# Top_Sheet.net
KiCad netlist of a schematic drawn in Altium Designer
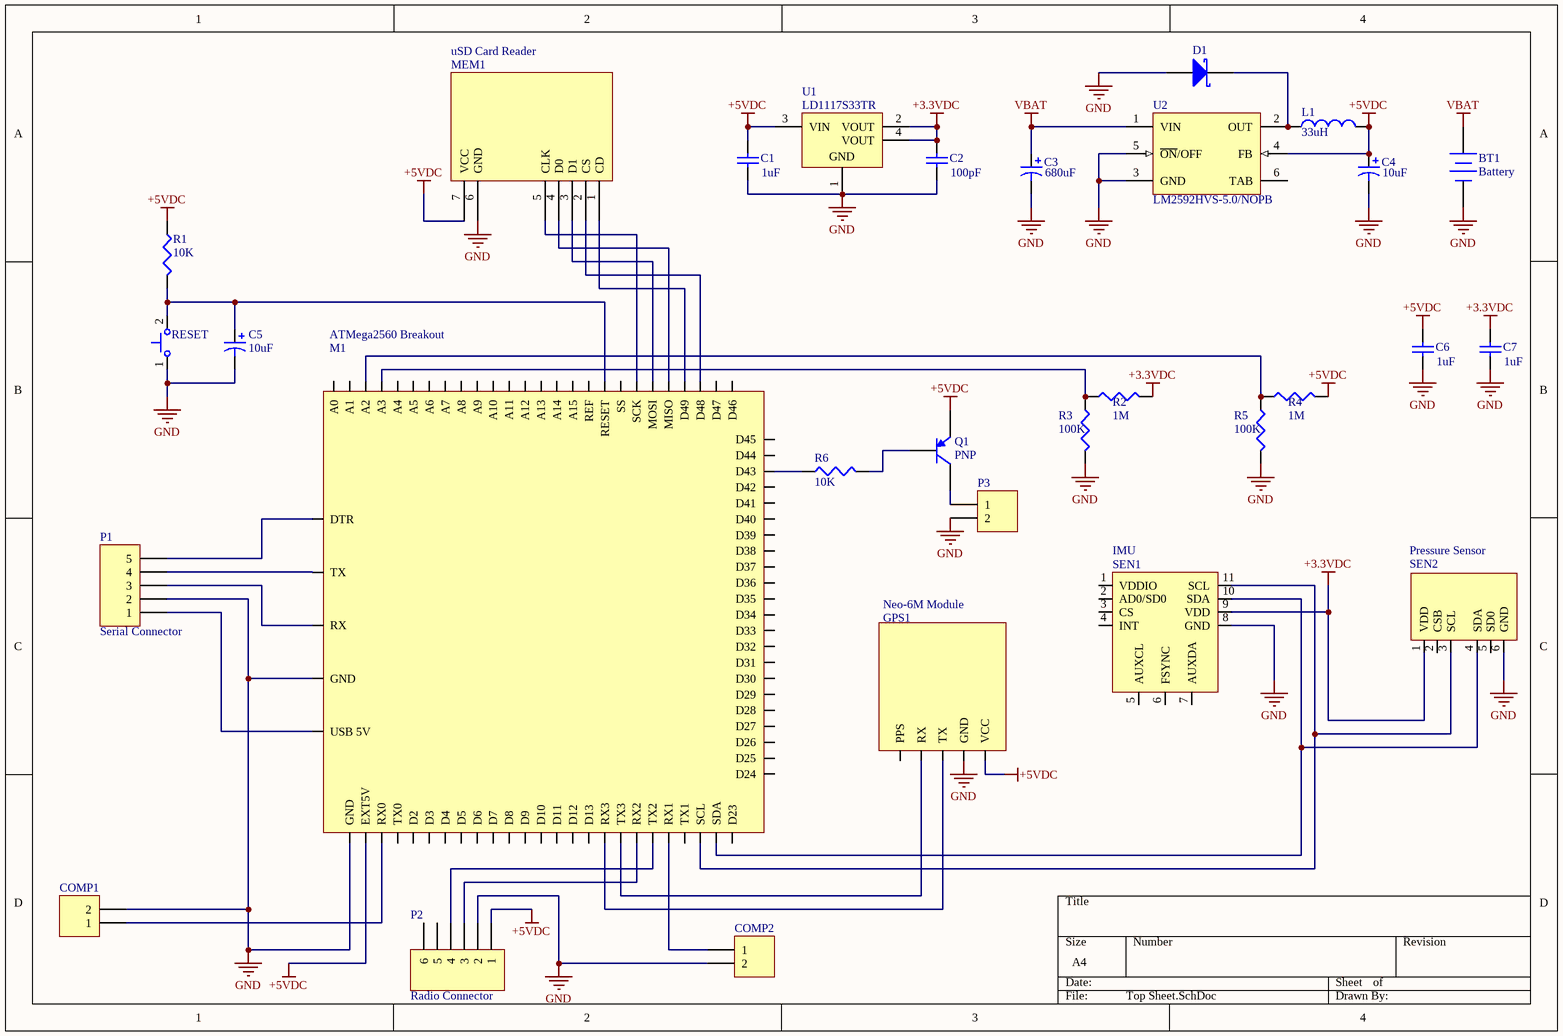
[diagram p0: Top Sheet.SchDoc]

(export (version "E")
  (design (tool "Eeschema 10.0.6"))
  (components
    (comp (ref "BT1")
      (value "Battery")
      (footprint "BAT-2")
      (description "Multicell Battery")
      (fields (field (name "PUBLISHER") "Altium Limited"))
      (libsource (lib "Miscellaneous Devices") (part "Battery"))
    )
    (comp (ref "C1")
      (value "1uF")
      (footprint "C1206")
      (description "Capacitor (Semiconductor SIM Model)")
      (fields (field (name "Comment") "Cap Semi") (field (name "PUBLISHER") "Altium Limited"))
      (libsource (lib "Miscellaneous Devices") (part "Cap Semi"))
    )
    (comp (ref "C2")
      (value "100pF")
      (footprint "C1206")
      (description "Capacitor (Semiconductor SIM Model)")
      (fields (field (name "Comment") "Cap Semi") (field (name "PUBLISHER") "Altium Limited"))
      (libsource (lib "Miscellaneous Devices") (part "Cap Semi"))
    )
    (comp (ref "C3")
      (value "680uF")
      (footprint "RB5-10.5")
      (description "Polarized Capacitor (Surface Mount)")
      (fields (field (name "Comment") "Cap Pol3") (field (name "PUBLISHER") "Altium Limited"))
      (libsource (lib "Miscellaneous Devices") (part "Cap Pol3"))
    )
    (comp (ref "C4")
      (value "10uF")
      (footprint "RB5-10.5")
      (description "Polarized Capacitor (Surface Mount)")
      (fields (field (name "Comment") "Cap Pol3") (field (name "PUBLISHER") "Altium Limited"))
      (libsource (lib "Miscellaneous Devices") (part "Cap Pol3"))
    )
    (comp (ref "C5")
      (value "10uF")
      (footprint "C0805")
      (description "Polarized Capacitor (Surface Mount)")
      (fields (field (name "Comment") "Cap Pol3") (field (name "PUBLISHER") "Altium Limited"))
      (libsource (lib "Miscellaneous Devices") (part "Cap Pol3"))
    )
    (comp (ref "C6")
      (value "1uF")
      (footprint "C1206")
      (description "Capacitor (Semiconductor SIM Model)")
      (fields (field (name "Comment") "Cap Semi") (field (name "PUBLISHER") "Altium Limited"))
      (libsource (lib "Miscellaneous Devices") (part "Cap Semi"))
    )
    (comp (ref "C7")
      (value "1uF")
      (footprint "C1206")
      (description "Capacitor (Semiconductor SIM Model)")
      (fields (field (name "Comment") "Cap Semi") (field (name "PUBLISHER") "Altium Limited"))
      (libsource (lib "Miscellaneous Devices") (part "Cap Semi"))
    )
    (comp (ref "COMP1")
      (value "Header 2")
      (footprint "HDR1X2")
      (description "Header, 2-Pin")
      (fields (field (name "PUBLISHER") "Altium Limited"))
      (libsource (lib "") (part "Header 2_1"))
    )
    (comp (ref "COMP2")
      (value "Header 2")
      (footprint "HDR1X2")
      (description "Header, 2-Pin")
      (fields (field (name "PUBLISHER") "Altium Limited"))
      (libsource (lib "Miscellaneous Connectors") (part "Header 2"))
    )
    (comp (ref "D1")
      (value "D Schottky")
      (footprint "SMB")
      (description "Schottky Diode")
      (fields (field (name "PUBLISHER") "Altium Limited"))
      (libsource (lib "Miscellaneous Devices") (part "D Schottky"))
    )
    (comp (ref "GPS1")
      (value "Neo-6M Module")
      (footprint "Neo-6M GPS Module")
      (description "Serial GPS module")
      (libsource (lib "SensorLib") (part "Neo-6M Module"))
    )
    (comp (ref "L1")
      (value "33uH")
      (footprint "Inductor")
      (description "Inductor")
      (fields (field (name "PUBLISHER") "Altium Limited"))
      (libsource (lib "Miscellaneous Devices") (part "Inductor"))
    )
    (comp (ref "M1")
      (value "ATMega2560 Breakout")
      (footprint "ATMEGA2560 Breakout")
      (description "Tindie's breakout board for the ATMega2560")
      (libsource (lib "SensorLib") (part "ATMega2560 Breakout"))
    )
    (comp (ref "MEM1")
      (value "uSD Card Reader")
      (footprint "uSD Card Reader")
      (description "SPI interface micro SD card reader from sparkfun.")
      (libsource (lib "SensorLib") (part "uSD Card Reader"))
    )
    (comp (ref "P1")
      (value "Serial Connector")
      (footprint "HDR1X5")
      (description "Header, 5-Pin")
      (fields (field (name "PUBLISHER") "Altium Limited"))
      (libsource (lib "Miscellaneous Connectors") (part "Header 5"))
    )
    (comp (ref "P2")
      (value "Radio Connector")
      (footprint "HDR1X6")
      (description "Header, 6-Pin")
      (fields (field (name "PUBLISHER") "Altium Limited"))
      (libsource (lib "Miscellaneous Connectors") (part "Header 6"))
    )
    (comp (ref "P3")
      (value "Header 2")
      (footprint "HDR1X2")
      (description "Header, 2-Pin")
      (fields (field (name "PUBLISHER") "Altium Limited"))
      (libsource (lib "Miscellaneous Connectors") (part "Header 2"))
    )
    (comp (ref "Q1")
      (value "PNP")
      (footprint "SOT-23B_N")
      (description "PNP Bipolar Transistor")
      (fields (field (name "PUBLISHER") "Altium Limited"))
      (libsource (lib "Miscellaneous Devices") (part "PNP"))
    )
    (comp (ref "R1")
      (value "10K")
      (footprint "6-0805_L")
      (description "Resistor")
      (fields (field (name "Comment") "Res3") (field (name "PUBLISHER") "Altium Limited"))
      (libsource (lib "Miscellaneous Devices") (part "Res3"))
    )
    (comp (ref "R2")
      (value "1M")
      (footprint "6-0805_L")
      (description "Resistor")
      (fields (field (name "Comment") "Res3") (field (name "PUBLISHER") "Altium Limited"))
      (libsource (lib "Miscellaneous Devices") (part "Res3"))
    )
    (comp (ref "R3")
      (value "100K")
      (footprint "6-0805_L")
      (description "Resistor")
      (fields (field (name "Comment") "Res3") (field (name "PUBLISHER") "Altium Limited"))
      (libsource (lib "Miscellaneous Devices") (part "Res3"))
    )
    (comp (ref "R4")
      (value "1M")
      (footprint "6-0805_L")
      (description "Resistor")
      (fields (field (name "Comment") "Res3") (field (name "PUBLISHER") "Altium Limited"))
      (libsource (lib "Miscellaneous Devices") (part "Res3"))
    )
    (comp (ref "R5")
      (value "100K")
      (footprint "6-0805_L")
      (description "Resistor")
      (fields (field (name "Comment") "Res3") (field (name "PUBLISHER") "Altium Limited"))
      (libsource (lib "Miscellaneous Devices") (part "Res3"))
    )
    (comp (ref "R6")
      (value "10K")
      (footprint "6-0805_L")
      (description "Resistor")
      (fields (field (name "Comment") "Res3") (field (name "PUBLISHER") "Altium Limited"))
      (libsource (lib "Miscellaneous Devices") (part "Res3"))
    )
    (comp (ref "RESET")
      (value "KSS221GLFS")
      (footprint "KSS-2G")
      (fields (field (name "PUBLISHER") "Altium Limited"))
      (libsource (lib "CK Switch") (part "KSS221GLFS"))
    )
    (comp (ref "SEN1")
      (value "IMU")
      (footprint "Sparkfun IMU")
      (description "MPU-9250 breakout board from sparkfun.")
      (libsource (lib "SensorLib") (part "Inertial Measurement Unit"))
    )
    (comp (ref "SEN2")
      (value "Pressure Sensor")
      (footprint "Barometric Pressure Sensor")
      (description "MS5611-01BA03 Barometric Pressure Sensor, Variometer.")
      (libsource (lib "SensorLib") (part "Baromateric Pressure Sensor"))
    )
    (comp (ref "U1")
      (value "LD1117S33TR")
      (footprint "SOT-223_N")
      (description "Fixed Low Drop Positive Voltage Regulator, 3.3V, 4-Pin SOT-223, Tape and Reel")
      (libsource (lib "STMicroelectronics Power Management Linear Regulator") (part "LD1117S33TR"))
    )
    (comp (ref "U2")
      (value "LM2592HVS-5.0/NOPB")
      (footprint "TS5B_N")
      (description "SIMPLE SWITCHER® Power Converter 150 KHz 2A Step-Down Voltage Regulator, 5-pin TO-263, Pb-Free")
      (fields
        (field (name "MANUFACTURER") "National Semiconductor")
        (field (name "PUBLISHER") "Altium Limited")
      )
      (libsource (lib "NSC Switcher") (part "LM2592HVS-5.0/NOPB"))
    )
  )
  (nets
    (net (code "1") (name "+3.3VDC") (class "Default")
      (node (ref "C2") (pin "2") (pinfunction "2_2") (pintype "passive"))
      (node (ref "C7") (pin "2") (pinfunction "2_2") (pintype "passive"))
      (node (ref "R2") (pin "2") (pinfunction "2_2") (pintype "passive"))
      (node (ref "SEN1") (pin "9") (pinfunction "VDD_9") (pintype "passive"))
      (node (ref "SEN2") (pin "1") (pinfunction "VDD_1") (pintype "passive"))
      (node (ref "U1") (pin "2") (pinfunction "VOUT_2") (pintype "power_in"))
      (node (ref "U1") (pin "4") (pinfunction "VOUT_4") (pintype "power_in"))
    )
    (net (code "2") (name "+5VDC") (class "Default")
      (node (ref "C1") (pin "2") (pinfunction "2_2") (pintype "passive"))
      (node (ref "C4") (pin "1") (pinfunction "1_1") (pintype "passive"))
      (node (ref "C6") (pin "2") (pinfunction "2_2") (pintype "passive"))
      (node (ref "GPS1") (pin "5") (pinfunction "VCC_5") (pintype "passive"))
      (node (ref "L1") (pin "2") (pinfunction "2_2") (pintype "passive"))
      (node (ref "M1") (pin "EXT5V") (pinfunction "EXT5V_EXT5V") (pintype "passive"))
      (node (ref "MEM1") (pin "7") (pinfunction "VCC_7") (pintype "passive"))
      (node (ref "P2") (pin "1") (pinfunction "1_1") (pintype "passive"))
      (node (ref "Q1") (pin "3") (pinfunction "E_3") (pintype "passive"))
      (node (ref "R1") (pin "1") (pinfunction "1_1") (pintype "passive"))
      (node (ref "R4") (pin "2") (pinfunction "2_2") (pintype "passive"))
      (node (ref "U1") (pin "3") (pinfunction "VIN_3") (pintype "power_in"))
      (node (ref "U2") (pin "4") (pinfunction "FB_4") (pintype "input"))
    )
    (net (code "3") (name "GND") (class "Default")
      (node (ref "BT1") (pin "2") (pinfunction "-_2") (pintype "passive"))
      (node (ref "C1") (pin "1") (pinfunction "1_1") (pintype "passive"))
      (node (ref "C2") (pin "1") (pinfunction "1_1") (pintype "passive"))
      (node (ref "C3") (pin "2") (pinfunction "2_2") (pintype "passive"))
      (node (ref "C4") (pin "2") (pinfunction "2_2") (pintype "passive"))
      (node (ref "C5") (pin "2") (pinfunction "2_2") (pintype "passive"))
      (node (ref "C6") (pin "1") (pinfunction "1_1") (pintype "passive"))
      (node (ref "C7") (pin "1") (pinfunction "1_1") (pintype "passive"))
      (node (ref "COMP1") (pin "2") (pinfunction "2_2") (pintype "passive"))
      (node (ref "COMP2") (pin "2") (pinfunction "2_2") (pintype "passive"))
      (node (ref "D1") (pin "1") (pinfunction "A_1") (pintype "passive"))
      (node (ref "GPS1") (pin "4") (pinfunction "GND_4") (pintype "passive"))
      (node (ref "M1") (pin "GND") (pinfunction "GND_GND") (pintype "passive"))
      (node (ref "MEM1") (pin "6") (pinfunction "GND_6") (pintype "passive"))
      (node (ref "P1") (pin "2") (pinfunction "2_2") (pintype "passive"))
      (node (ref "P2") (pin "2") (pinfunction "2_2") (pintype "passive"))
      (node (ref "P3") (pin "2") (pinfunction "2_2") (pintype "passive"))
      (node (ref "R3") (pin "2") (pinfunction "2_2") (pintype "passive"))
      (node (ref "R5") (pin "2") (pinfunction "2_2") (pintype "passive"))
      (node (ref "RESET") (pin "1") (pinfunction "1_1") (pintype "passive"))
      (node (ref "SEN1") (pin "8") (pinfunction "GND_8") (pintype "passive"))
      (node (ref "SEN2") (pin "6") (pinfunction "GND_6") (pintype "passive"))
      (node (ref "U1") (pin "1") (pinfunction "GND_1") (pintype "power_in"))
      (node (ref "U2") (pin "3") (pinfunction "GND_3") (pintype "power_in"))
      (node (ref "U2") (pin "5") (pinfunction "~{ON}/OFF_5") (pintype "input"))
    )
    (net (code "4") (name "Net-(C5-Pad1)") (class "Default")
      (node (ref "C5") (pin "1") (pinfunction "1_1") (pintype "passive"))
      (node (ref "M1") (pin "RESET") (pinfunction "RESET_RESET") (pintype "passive"))
      (node (ref "R1") (pin "2") (pinfunction "2_2") (pintype "passive"))
      (node (ref "RESET") (pin "2") (pinfunction "2_2") (pintype "passive"))
    )
    (net (code "5") (name "Net-(COMP1-Pad1)") (class "Default")
      (node (ref "COMP1") (pin "1") (pinfunction "1_1") (pintype "passive"))
      (node (ref "M1") (pin "RX0") (pinfunction "RX0_RX0") (pintype "passive"))
    )
    (net (code "6") (name "Net-(COMP2-Pad1)") (class "Default")
      (node (ref "COMP2") (pin "1") (pinfunction "1_1") (pintype "passive"))
      (node (ref "M1") (pin "RX1") (pinfunction "RX1_RX1") (pintype "passive"))
    )
    (net (code "7") (name "Net-(D1-K)") (class "Default")
      (node (ref "D1") (pin "2") (pinfunction "K_2") (pintype "passive"))
      (node (ref "L1") (pin "1") (pinfunction "1_1") (pintype "passive"))
      (node (ref "U2") (pin "2") (pinfunction "OUT_2") (pintype "power_in"))
    )
    (net (code "8") (name "Net-(GPS1-RX)") (class "Default")
      (node (ref "GPS1") (pin "2") (pinfunction "RX_2") (pintype "passive"))
      (node (ref "M1") (pin "TX3") (pinfunction "TX3_TX3") (pintype "passive"))
    )
    (net (code "9") (name "Net-(GPS1-TX)") (class "Default")
      (node (ref "GPS1") (pin "3") (pinfunction "TX_3") (pintype "passive"))
      (node (ref "M1") (pin "RX3") (pinfunction "RX3_RX3") (pintype "passive"))
    )
    (net (code "10") (name "Net-(M1-D43)") (class "Default")
      (node (ref "M1") (pin "43") (pinfunction "D43_43") (pintype "passive"))
      (node (ref "R6") (pin "1") (pinfunction "1_1") (pintype "passive"))
    )
    (net (code "11") (name "Net-(M1-D48)") (class "Default")
      (node (ref "M1") (pin "48") (pinfunction "D48_48") (pintype "passive"))
      (node (ref "MEM1") (pin "2") (pinfunction "CS_2") (pintype "passive"))
    )
    (net (code "12") (name "Net-(M1-D49)") (class "Default")
      (node (ref "M1") (pin "49") (pinfunction "D49_49") (pintype "passive"))
      (node (ref "MEM1") (pin "1") (pinfunction "CD_1") (pintype "passive"))
    )
    (net (code "13") (name "Net-(M1-PadA2)") (class "Default")
      (node (ref "M1") (pin "A2") (pinfunction "A2_A2") (pintype "passive"))
      (node (ref "R4") (pin "1") (pinfunction "1_1") (pintype "passive"))
      (node (ref "R5") (pin "1") (pinfunction "1_1") (pintype "passive"))
    )
    (net (code "14") (name "Net-(M1-PadA3)") (class "Default")
      (node (ref "M1") (pin "A3") (pinfunction "A3_A3") (pintype "passive"))
      (node (ref "R2") (pin "1") (pinfunction "1_1") (pintype "passive"))
      (node (ref "R3") (pin "1") (pinfunction "1_1") (pintype "passive"))
    )
    (net (code "15") (name "Net-(M1-PadDTR)") (class "Default")
      (node (ref "M1") (pin "DTR") (pinfunction "DTR_DTR") (pintype "passive"))
      (node (ref "P1") (pin "5") (pinfunction "5_5") (pintype "passive"))
    )
    (net (code "16") (name "Net-(M1-PadRX)") (class "Default")
      (node (ref "M1") (pin "RX") (pinfunction "RX_RX") (pintype "passive"))
      (node (ref "P1") (pin "3") (pinfunction "3_3") (pintype "passive"))
    )
    (net (code "17") (name "Net-(M1-PadRX2)") (class "Default")
      (node (ref "M1") (pin "RX2") (pinfunction "RX2_RX2") (pintype "passive"))
      (node (ref "P2") (pin "3") (pinfunction "3_3") (pintype "passive"))
    )
    (net (code "18") (name "Net-(M1-PadTX)") (class "Default")
      (node (ref "M1") (pin "TX") (pinfunction "TX_TX") (pintype "passive"))
      (node (ref "P1") (pin "4") (pinfunction "4_4") (pintype "passive"))
    )
    (net (code "19") (name "Net-(M1-PadTX2)") (class "Default")
      (node (ref "M1") (pin "TX2") (pinfunction "TX2_TX2") (pintype "passive"))
      (node (ref "P2") (pin "4") (pinfunction "4_4") (pintype "passive"))
    )
    (net (code "20") (name "Net-(M1-PadUSB_5V)") (class "Default")
      (node (ref "M1") (pin "USB_5V") (pinfunction "USB_5V_USB_5V") (pintype "passive"))
      (node (ref "P1") (pin "1") (pinfunction "1_1") (pintype "passive"))
    )
    (net (code "21") (name "Net-(MEM1-CLK)") (class "Default")
      (node (ref "M1") (pin "SCK") (pinfunction "SCK_SCK") (pintype "passive"))
      (node (ref "MEM1") (pin "5") (pinfunction "CLK_5") (pintype "passive"))
    )
    (net (code "22") (name "Net-(MEM1-D0)") (class "Default")
      (node (ref "M1") (pin "MISO") (pinfunction "MISO_MISO") (pintype "passive"))
      (node (ref "MEM1") (pin "4") (pinfunction "D0_4") (pintype "passive"))
    )
    (net (code "23") (name "Net-(MEM1-D1)") (class "Default")
      (node (ref "M1") (pin "MOSI") (pinfunction "MOSI_MOSI") (pintype "passive"))
      (node (ref "MEM1") (pin "3") (pinfunction "D1_3") (pintype "passive"))
    )
    (net (code "24") (name "Net-(Q1-B)") (class "Default")
      (node (ref "Q1") (pin "2") (pinfunction "B_2") (pintype "passive"))
      (node (ref "R6") (pin "2") (pinfunction "2_2") (pintype "passive"))
    )
    (net (code "25") (name "Net-(Q1-C)") (class "Default")
      (node (ref "P3") (pin "1") (pinfunction "1_1") (pintype "passive"))
      (node (ref "Q1") (pin "1") (pinfunction "C_1") (pintype "passive"))
    )
    (net (code "26") (name "Net-(SEN1-SCL)") (class "Default")
      (node (ref "M1") (pin "SCL") (pinfunction "SCL_SCL") (pintype "passive"))
      (node (ref "SEN1") (pin "11") (pinfunction "SCL_11") (pintype "passive"))
      (node (ref "SEN2") (pin "3") (pinfunction "SCL_3") (pintype "passive"))
    )
    (net (code "27") (name "Net-(SEN1-SDA)") (class "Default")
      (node (ref "M1") (pin "SDA") (pinfunction "SDA_SDA") (pintype "passive"))
      (node (ref "SEN1") (pin "10") (pinfunction "SDA_10") (pintype "passive"))
      (node (ref "SEN2") (pin "4") (pinfunction "SDA_4") (pintype "passive"))
    )
    (net (code "28") (name "VBAT") (class "Default")
      (node (ref "BT1") (pin "1") (pinfunction "+_1") (pintype "passive"))
      (node (ref "C3") (pin "1") (pinfunction "1_1") (pintype "passive"))
      (node (ref "U2") (pin "1") (pinfunction "VIN_1") (pintype "power_in"))
    )
    (net (code "29") (name "unconnected-(GPS1-PPS-Pad1)") (class "Default")
      (node (ref "GPS1") (pin "1") (pinfunction "PPS_1") (pintype "passive"))
    )
    (net (code "30") (name "unconnected-(M1-D2-Pad2)") (class "Default")
      (node (ref "M1") (pin "2") (pinfunction "D2_2") (pintype "passive"))
    )
    (net (code "31") (name "unconnected-(M1-D3-Pad3)") (class "Default")
      (node (ref "M1") (pin "3") (pinfunction "D3_3") (pintype "passive"))
    )
    (net (code "32") (name "unconnected-(M1-D4-Pad4)") (class "Default")
      (node (ref "M1") (pin "4") (pinfunction "D4_4") (pintype "passive"))
    )
    (net (code "33") (name "unconnected-(M1-D5-Pad5)") (class "Default")
      (node (ref "M1") (pin "5") (pinfunction "D5_5") (pintype "passive"))
    )
    (net (code "34") (name "unconnected-(M1-D6-Pad6)") (class "Default")
      (node (ref "M1") (pin "6") (pinfunction "D6_6") (pintype "passive"))
    )
    (net (code "35") (name "unconnected-(M1-D7-Pad7)") (class "Default")
      (node (ref "M1") (pin "7") (pinfunction "D7_7") (pintype "passive"))
    )
    (net (code "36") (name "unconnected-(M1-D8-Pad8)") (class "Default")
      (node (ref "M1") (pin "8") (pinfunction "D8_8") (pintype "passive"))
    )
    (net (code "37") (name "unconnected-(M1-D9-Pad9)") (class "Default")
      (node (ref "M1") (pin "9") (pinfunction "D9_9") (pintype "passive"))
    )
    (net (code "38") (name "unconnected-(M1-D10-Pad10)") (class "Default")
      (node (ref "M1") (pin "10") (pinfunction "D10_10") (pintype "passive"))
    )
    (net (code "39") (name "unconnected-(M1-D11-Pad11)") (class "Default")
      (node (ref "M1") (pin "11") (pinfunction "D11_11") (pintype "passive"))
    )
    (net (code "40") (name "unconnected-(M1-D12-Pad12)") (class "Default")
      (node (ref "M1") (pin "12") (pinfunction "D12_12") (pintype "passive"))
    )
    (net (code "41") (name "unconnected-(M1-D13-Pad13)") (class "Default")
      (node (ref "M1") (pin "13") (pinfunction "D13_13") (pintype "passive"))
    )
    (net (code "42") (name "unconnected-(M1-D23-Pad23)") (class "Default")
      (node (ref "M1") (pin "23") (pinfunction "D23_23") (pintype "passive"))
    )
    (net (code "43") (name "unconnected-(M1-D24-Pad24)") (class "Default")
      (node (ref "M1") (pin "24") (pinfunction "D24_24") (pintype "passive"))
    )
    (net (code "44") (name "unconnected-(M1-D25-Pad25)") (class "Default")
      (node (ref "M1") (pin "25") (pinfunction "D25_25") (pintype "passive"))
    )
    (net (code "45") (name "unconnected-(M1-D26-Pad26)") (class "Default")
      (node (ref "M1") (pin "26") (pinfunction "D26_26") (pintype "passive"))
    )
    (net (code "46") (name "unconnected-(M1-D27-Pad27)") (class "Default")
      (node (ref "M1") (pin "27") (pinfunction "D27_27") (pintype "passive"))
    )
    (net (code "47") (name "unconnected-(M1-D28-Pad28)") (class "Default")
      (node (ref "M1") (pin "28") (pinfunction "D28_28") (pintype "passive"))
    )
    (net (code "48") (name "unconnected-(M1-D29-Pad29)") (class "Default")
      (node (ref "M1") (pin "29") (pinfunction "D29_29") (pintype "passive"))
    )
    (net (code "49") (name "unconnected-(M1-D30-Pad30)") (class "Default")
      (node (ref "M1") (pin "30") (pinfunction "D30_30") (pintype "passive"))
    )
    (net (code "50") (name "unconnected-(M1-D31-Pad31)") (class "Default")
      (node (ref "M1") (pin "31") (pinfunction "D31_31") (pintype "passive"))
    )
    (net (code "51") (name "unconnected-(M1-D32-Pad32)") (class "Default")
      (node (ref "M1") (pin "32") (pinfunction "D32_32") (pintype "passive"))
    )
    (net (code "52") (name "unconnected-(M1-D33-Pad33)") (class "Default")
      (node (ref "M1") (pin "33") (pinfunction "D33_33") (pintype "passive"))
    )
    (net (code "53") (name "unconnected-(M1-D34-Pad34)") (class "Default")
      (node (ref "M1") (pin "34") (pinfunction "D34_34") (pintype "passive"))
    )
    (net (code "54") (name "unconnected-(M1-D35-Pad35)") (class "Default")
      (node (ref "M1") (pin "35") (pinfunction "D35_35") (pintype "passive"))
    )
    (net (code "55") (name "unconnected-(M1-D36-Pad36)") (class "Default")
      (node (ref "M1") (pin "36") (pinfunction "D36_36") (pintype "passive"))
    )
    (net (code "56") (name "unconnected-(M1-D37-Pad37)") (class "Default")
      (node (ref "M1") (pin "37") (pinfunction "D37_37") (pintype "passive"))
    )
    (net (code "57") (name "unconnected-(M1-D38-Pad38)") (class "Default")
      (node (ref "M1") (pin "38") (pinfunction "D38_38") (pintype "passive"))
    )
    (net (code "58") (name "unconnected-(M1-D39-Pad39)") (class "Default")
      (node (ref "M1") (pin "39") (pinfunction "D39_39") (pintype "passive"))
    )
    (net (code "59") (name "unconnected-(M1-D40-Pad40)") (class "Default")
      (node (ref "M1") (pin "40") (pinfunction "D40_40") (pintype "passive"))
    )
    (net (code "60") (name "unconnected-(M1-D41-Pad41)") (class "Default")
      (node (ref "M1") (pin "41") (pinfunction "D41_41") (pintype "passive"))
    )
    (net (code "61") (name "unconnected-(M1-D42-Pad42)") (class "Default")
      (node (ref "M1") (pin "42") (pinfunction "D42_42") (pintype "passive"))
    )
    (net (code "62") (name "unconnected-(M1-D44-Pad44)") (class "Default")
      (node (ref "M1") (pin "44") (pinfunction "D44_44") (pintype "passive"))
    )
    (net (code "63") (name "unconnected-(M1-D45-Pad45)") (class "Default")
      (node (ref "M1") (pin "45") (pinfunction "D45_45") (pintype "passive"))
    )
    (net (code "64") (name "unconnected-(M1-D46-Pad46)") (class "Default")
      (node (ref "M1") (pin "46") (pinfunction "D46_46") (pintype "passive"))
    )
    (net (code "65") (name "unconnected-(M1-D47-Pad47)") (class "Default")
      (node (ref "M1") (pin "47") (pinfunction "D47_47") (pintype "passive"))
    )
    (net (code "66") (name "unconnected-(M1-PadA0)") (class "Default")
      (node (ref "M1") (pin "A0") (pinfunction "A0_A0") (pintype "passive"))
    )
    (net (code "67") (name "unconnected-(M1-PadA1)") (class "Default")
      (node (ref "M1") (pin "A1") (pinfunction "A1_A1") (pintype "passive"))
    )
    (net (code "68") (name "unconnected-(M1-PadA4)") (class "Default")
      (node (ref "M1") (pin "A4") (pinfunction "A4_A4") (pintype "passive"))
    )
    (net (code "69") (name "unconnected-(M1-PadA5)") (class "Default")
      (node (ref "M1") (pin "A5") (pinfunction "A5_A5") (pintype "passive"))
    )
    (net (code "70") (name "unconnected-(M1-PadA6)") (class "Default")
      (node (ref "M1") (pin "A6") (pinfunction "A6_A6") (pintype "passive"))
    )
    (net (code "71") (name "unconnected-(M1-PadA7)") (class "Default")
      (node (ref "M1") (pin "A7") (pinfunction "A7_A7") (pintype "passive"))
    )
    (net (code "72") (name "unconnected-(M1-PadA8)") (class "Default")
      (node (ref "M1") (pin "A8") (pinfunction "A8_A8") (pintype "passive"))
    )
    (net (code "73") (name "unconnected-(M1-PadA9)") (class "Default")
      (node (ref "M1") (pin "A9") (pinfunction "A9_A9") (pintype "passive"))
    )
    (net (code "74") (name "unconnected-(M1-PadA10)") (class "Default")
      (node (ref "M1") (pin "A10") (pinfunction "A10_A10") (pintype "passive"))
    )
    (net (code "75") (name "unconnected-(M1-PadA11)") (class "Default")
      (node (ref "M1") (pin "A11") (pinfunction "A11_A11") (pintype "passive"))
    )
    (net (code "76") (name "unconnected-(M1-PadA12)") (class "Default")
      (node (ref "M1") (pin "A12") (pinfunction "A12_A12") (pintype "passive"))
    )
    (net (code "77") (name "unconnected-(M1-PadA13)") (class "Default")
      (node (ref "M1") (pin "A13") (pinfunction "A13_A13") (pintype "passive"))
    )
    (net (code "78") (name "unconnected-(M1-PadA14)") (class "Default")
      (node (ref "M1") (pin "A14") (pinfunction "A14_A14") (pintype "passive"))
    )
    (net (code "79") (name "unconnected-(M1-PadA15)") (class "Default")
      (node (ref "M1") (pin "A15") (pinfunction "A15_A15") (pintype "passive"))
    )
    (net (code "80") (name "unconnected-(M1-PadREF)") (class "Default")
      (node (ref "M1") (pin "REF") (pinfunction "REF_REF") (pintype "passive"))
    )
    (net (code "81") (name "unconnected-(M1-PadSS)") (class "Default")
      (node (ref "M1") (pin "SS") (pinfunction "SS_SS") (pintype "passive"))
    )
    (net (code "82") (name "unconnected-(M1-PadTX0)") (class "Default")
      (node (ref "M1") (pin "TX0") (pinfunction "TX0_TX0") (pintype "passive"))
    )
    (net (code "83") (name "unconnected-(M1-PadTX1)") (class "Default")
      (node (ref "M1") (pin "TX1") (pinfunction "TX1_TX1") (pintype "passive"))
    )
    (net (code "84") (name "unconnected-(P2-Pad5)") (class "Default")
      (node (ref "P2") (pin "5") (pinfunction "5_5") (pintype "passive"))
    )
    (net (code "85") (name "unconnected-(P2-Pad6)") (class "Default")
      (node (ref "P2") (pin "6") (pinfunction "6_6") (pintype "passive"))
    )
    (net (code "86") (name "unconnected-(SEN1-AD0{slash}SD0-Pad2)") (class "Default")
      (node (ref "SEN1") (pin "2") (pinfunction "AD0/SD0_2") (pintype "passive"))
    )
    (net (code "87") (name "unconnected-(SEN1-AUXCL-Pad5)") (class "Default")
      (node (ref "SEN1") (pin "5") (pinfunction "AUXCL_5") (pintype "passive"))
    )
    (net (code "88") (name "unconnected-(SEN1-AUXDA-Pad7)") (class "Default")
      (node (ref "SEN1") (pin "7") (pinfunction "AUXDA_7") (pintype "passive"))
    )
    (net (code "89") (name "unconnected-(SEN1-CS-Pad3)") (class "Default")
      (node (ref "SEN1") (pin "3") (pinfunction "CS_3") (pintype "passive"))
    )
    (net (code "90") (name "unconnected-(SEN1-FSYNC-Pad6)") (class "Default")
      (node (ref "SEN1") (pin "6") (pinfunction "FSYNC_6") (pintype "passive"))
    )
    (net (code "91") (name "unconnected-(SEN1-INT-Pad4)") (class "Default")
      (node (ref "SEN1") (pin "4") (pinfunction "INT_4") (pintype "passive"))
    )
    (net (code "92") (name "unconnected-(SEN1-VDDIO-Pad1)") (class "Default")
      (node (ref "SEN1") (pin "1") (pinfunction "VDDIO_1") (pintype "passive"))
    )
    (net (code "93") (name "unconnected-(SEN2-CSB-Pad2)") (class "Default")
      (node (ref "SEN2") (pin "2") (pinfunction "CSB_2") (pintype "passive"))
    )
    (net (code "94") (name "unconnected-(SEN2-SD0-Pad5)") (class "Default")
      (node (ref "SEN2") (pin "5") (pinfunction "SD0_5") (pintype "passive"))
    )
    (net (code "95") (name "unconnected-(U2-TAB-Pad6)") (class "Default")
      (node (ref "U2") (pin "6") (pinfunction "TAB_6") (pintype "power_in"))
    )
  )
)
